# MT6816_Angle_Encoder.net
KiCad netlist of a schematic drawn in Altium Designer
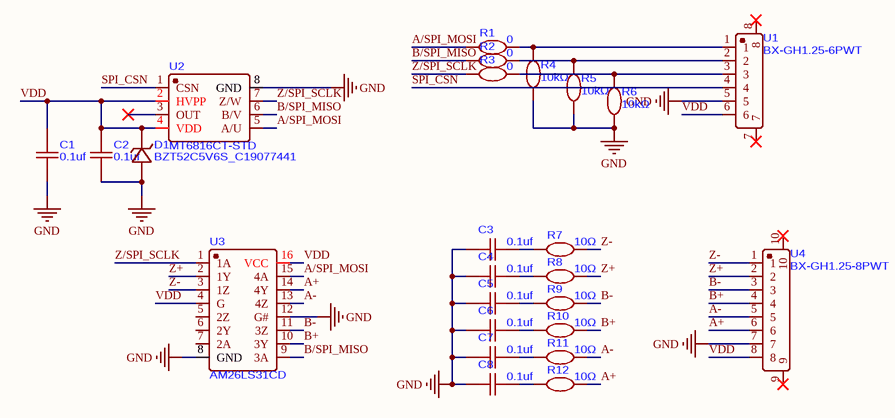
[diagram p0: MT6816_Angle_Encoder.SchDoc]

(export (version "E")
  (design (tool "Eeschema 10.0.6"))
  (components
    (comp (ref "C1")
      (value "0.1uf")
      (footprint "C0402")
      (libsource (lib "MT6816_Angle_Encoder") (part "CC0402KRX6S5BB225"))
    )
    (comp (ref "C2")
      (value "0.1uf")
      (footprint "C0402")
      (libsource (lib "MT6816_Angle_Encoder") (part "CC0402KRX6S5BB225"))
    )
    (comp (ref "C3")
      (value "0.1uf")
      (footprint "C0402")
      (libsource (lib "MT6816_Angle_Encoder") (part "CC0402KRX6S5BB225"))
    )
    (comp (ref "C4")
      (value "0.1uf")
      (footprint "C0402")
      (libsource (lib "MT6816_Angle_Encoder") (part "CC0402KRX6S5BB225"))
    )
    (comp (ref "C5")
      (value "0.1uf")
      (footprint "C0402")
      (libsource (lib "MT6816_Angle_Encoder") (part "CC0402KRX6S5BB225"))
    )
    (comp (ref "C6")
      (value "0.1uf")
      (footprint "C0402")
      (libsource (lib "MT6816_Angle_Encoder") (part "CC0402KRX6S5BB225"))
    )
    (comp (ref "C7")
      (value "0.1uf")
      (footprint "C0402")
      (libsource (lib "MT6816_Angle_Encoder") (part "CC0402KRX6S5BB225"))
    )
    (comp (ref "C8")
      (value "0.1uf")
      (footprint "C0402")
      (libsource (lib "MT6816_Angle_Encoder") (part "CC0402KRX6S5BB225"))
    )
    (comp (ref "D1")
      (value "BZT52C5V6S_C19077441")
      (footprint "SOD-323_L1.7-W1.3-LS2.6-RD")
      (libsource (lib "MT6816_Angle_Encoder") (part "BZT52C5V6S_C19077441"))
    )
    (comp (ref "R1")
      (value "0")
      (footprint "R0402")
      (libsource (lib "MT6816_Angle_Encoder") (part "PTFR0402B30K0P9"))
    )
    (comp (ref "R2")
      (value "0")
      (footprint "R0402")
      (libsource (lib "MT6816_Angle_Encoder") (part "PTFR0402B30K0P9"))
    )
    (comp (ref "R3")
      (value "0")
      (footprint "R0402")
      (libsource (lib "MT6816_Angle_Encoder") (part "PTFR0402B30K0P9"))
    )
    (comp (ref "R4")
      (value "10kΩ")
      (footprint "R0402")
      (libsource (lib "MT6816_Angle_Encoder") (part "PTFR0402B30K0P9"))
    )
    (comp (ref "R5")
      (value "10kΩ")
      (footprint "R0402")
      (libsource (lib "MT6816_Angle_Encoder") (part "PTFR0402B30K0P9"))
    )
    (comp (ref "R6")
      (value "10kΩ")
      (footprint "R0402")
      (libsource (lib "MT6816_Angle_Encoder") (part "PTFR0402B30K0P9"))
    )
    (comp (ref "R7")
      (value "10Ω")
      (footprint "R0402")
      (libsource (lib "MT6816_Angle_Encoder") (part "PTFR0402B30K0P9"))
    )
    (comp (ref "R8")
      (value "10Ω")
      (footprint "R0402")
      (libsource (lib "MT6816_Angle_Encoder") (part "PTFR0402B30K0P9"))
    )
    (comp (ref "R9")
      (value "10Ω")
      (footprint "R0402")
      (libsource (lib "MT6816_Angle_Encoder") (part "PTFR0402B30K0P9"))
    )
    (comp (ref "R10")
      (value "10Ω")
      (footprint "R0402")
      (libsource (lib "MT6816_Angle_Encoder") (part "PTFR0402B30K0P9"))
    )
    (comp (ref "R11")
      (value "10Ω")
      (footprint "R0402")
      (libsource (lib "MT6816_Angle_Encoder") (part "PTFR0402B30K0P9"))
    )
    (comp (ref "R12")
      (value "10Ω")
      (footprint "R0402")
      (libsource (lib "MT6816_Angle_Encoder") (part "PTFR0402B30K0P9"))
    )
    (comp (ref "U1")
      (value "BX-GH1.25-6PWT")
      (footprint "CONN-SMD_6P-P1.25_BX-GH1.25-6PWT")
      (libsource (lib "MT6816_Angle_Encoder") (part "BX-GH1.25-6PWT"))
    )
    (comp (ref "U2")
      (value "MT6816CT-STD")
      (footprint "SOP-8_L4.9-W3.9-P1.27-LS6.0-BL")
      (libsource (lib "MT6816_Angle_Encoder") (part "MT6816CT-STD"))
    )
    (comp (ref "U3")
      (value "AM26LS31CD")
      (footprint "SOIC-16_L9.9-W3.9-P1.27-LS6.0-BL")
      (libsource (lib "MT6816_Angle_Encoder") (part "AM26LS31CD"))
    )
    (comp (ref "U4")
      (value "BX-GH1.25-8PWT")
      (footprint "CONN-SMD_8P-P1.25_BX-GH1.25-8PWT")
      (libsource (lib "MT6816_Angle_Encoder") (part "BX-GH1.25-8PWT"))
    )
  )
  (nets
    (net (code "1") (name "/A+") (class "Default")
      (node (ref "R12") (pin "2") (pinfunction "2_2") (pintype "passive"))
      (node (ref "U3") (pin "14") (pinfunction "4Y_14") (pintype "passive"))
      (node (ref "U4") (pin "6") (pinfunction "6_6") (pintype "passive"))
    )
    (net (code "2") (name "/A-") (class "Default")
      (node (ref "R11") (pin "2") (pinfunction "2_2") (pintype "passive"))
      (node (ref "U3") (pin "13") (pinfunction "4Z_13") (pintype "passive"))
      (node (ref "U4") (pin "5") (pinfunction "5_5") (pintype "passive"))
    )
    (net (code "3") (name "/A{slash}SPI_MOSI") (class "Default")
      (node (ref "R1") (pin "2") (pinfunction "2_2") (pintype "passive"))
      (node (ref "U2") (pin "5") (pinfunction "A/U_5") (pintype "passive"))
      (node (ref "U3") (pin "15") (pinfunction "4A_15") (pintype "passive"))
    )
    (net (code "4") (name "/B+") (class "Default")
      (node (ref "R10") (pin "2") (pinfunction "2_2") (pintype "passive"))
      (node (ref "U3") (pin "10") (pinfunction "3Y_10") (pintype "passive"))
      (node (ref "U4") (pin "4") (pinfunction "4_4") (pintype "passive"))
    )
    (net (code "5") (name "/B-") (class "Default")
      (node (ref "R9") (pin "2") (pinfunction "2_2") (pintype "passive"))
      (node (ref "U3") (pin "11") (pinfunction "3Z_11") (pintype "passive"))
      (node (ref "U4") (pin "3") (pinfunction "3_3") (pintype "passive"))
    )
    (net (code "6") (name "/B{slash}SPI_MISO") (class "Default")
      (node (ref "R2") (pin "2") (pinfunction "2_2") (pintype "passive"))
      (node (ref "U2") (pin "6") (pinfunction "B/V_6") (pintype "passive"))
      (node (ref "U3") (pin "9") (pinfunction "3A_9") (pintype "passive"))
    )
    (net (code "7") (name "/SPI_CSN") (class "Default")
      (node (ref "U1") (pin "4") (pinfunction "4_4") (pintype "passive"))
      (node (ref "U2") (pin "1") (pinfunction "CSN_1") (pintype "passive"))
    )
    (net (code "8") (name "/VDD") (class "Default")
      (node (ref "C1") (pin "2") (pinfunction "2_2") (pintype "passive"))
      (node (ref "C2") (pin "2") (pinfunction "2_2") (pintype "passive"))
      (node (ref "D1") (pin "1") (pinfunction "K_1") (pintype "passive"))
      (node (ref "U1") (pin "6") (pinfunction "6_6") (pintype "passive"))
      (node (ref "U2") (pin "2") (pinfunction "HVPP_2") (pintype "passive"))
      (node (ref "U2") (pin "4") (pinfunction "VDD_4") (pintype "passive"))
      (node (ref "U3") (pin "16") (pinfunction "VCC_16") (pintype "passive"))
      (node (ref "U3") (pin "4") (pinfunction "G_4") (pintype "passive"))
      (node (ref "U4") (pin "8") (pinfunction "8_8") (pintype "passive"))
    )
    (net (code "9") (name "/Z+") (class "Default")
      (node (ref "R8") (pin "2") (pinfunction "2_2") (pintype "passive"))
      (node (ref "U3") (pin "2") (pinfunction "1Y_2") (pintype "passive"))
      (node (ref "U4") (pin "2") (pinfunction "2_2") (pintype "passive"))
    )
    (net (code "10") (name "/Z-") (class "Default")
      (node (ref "R7") (pin "2") (pinfunction "2_2") (pintype "passive"))
      (node (ref "U3") (pin "3") (pinfunction "1Z_3") (pintype "passive"))
      (node (ref "U4") (pin "1") (pinfunction "1_1") (pintype "passive"))
    )
    (net (code "11") (name "/Z{slash}SPI_SCLK") (class "Default")
      (node (ref "R3") (pin "2") (pinfunction "2_2") (pintype "passive"))
      (node (ref "U2") (pin "7") (pinfunction "Z/W_7") (pintype "passive"))
      (node (ref "U3") (pin "1") (pinfunction "1A_1") (pintype "passive"))
    )
    (net (code "12") (name "GND") (class "Default")
      (node (ref "C1") (pin "1") (pinfunction "1_1") (pintype "passive"))
      (node (ref "C2") (pin "1") (pinfunction "1_1") (pintype "passive"))
      (node (ref "C3") (pin "1") (pinfunction "1_1") (pintype "passive"))
      (node (ref "C4") (pin "1") (pinfunction "1_1") (pintype "passive"))
      (node (ref "C5") (pin "1") (pinfunction "1_1") (pintype "passive"))
      (node (ref "C6") (pin "1") (pinfunction "1_1") (pintype "passive"))
      (node (ref "C7") (pin "1") (pinfunction "1_1") (pintype "passive"))
      (node (ref "C8") (pin "1") (pinfunction "1_1") (pintype "passive"))
      (node (ref "D1") (pin "2") (pinfunction "A_2") (pintype "passive"))
      (node (ref "R4") (pin "1") (pinfunction "1_1") (pintype "passive"))
      (node (ref "R5") (pin "1") (pinfunction "1_1") (pintype "passive"))
      (node (ref "R6") (pin "1") (pinfunction "1_1") (pintype "passive"))
      (node (ref "U1") (pin "5") (pinfunction "5_5") (pintype "passive"))
      (node (ref "U2") (pin "8") (pinfunction "GND_8") (pintype "passive"))
      (node (ref "U3") (pin "12") (pinfunction "G#_12") (pintype "passive"))
      (node (ref "U3") (pin "8") (pinfunction "GND_8") (pintype "passive"))
      (node (ref "U4") (pin "7") (pinfunction "7_7") (pintype "passive"))
    )
    (net (code "13") (name "Net-(C3-Pad2)") (class "Default")
      (node (ref "C3") (pin "2") (pinfunction "2_2") (pintype "passive"))
      (node (ref "R7") (pin "1") (pinfunction "1_1") (pintype "passive"))
    )
    (net (code "14") (name "Net-(C4-Pad2)") (class "Default")
      (node (ref "C4") (pin "2") (pinfunction "2_2") (pintype "passive"))
      (node (ref "R8") (pin "1") (pinfunction "1_1") (pintype "passive"))
    )
    (net (code "15") (name "Net-(C5-Pad2)") (class "Default")
      (node (ref "C5") (pin "2") (pinfunction "2_2") (pintype "passive"))
      (node (ref "R9") (pin "1") (pinfunction "1_1") (pintype "passive"))
    )
    (net (code "16") (name "Net-(C6-Pad2)") (class "Default")
      (node (ref "C6") (pin "2") (pinfunction "2_2") (pintype "passive"))
      (node (ref "R10") (pin "1") (pinfunction "1_1") (pintype "passive"))
    )
    (net (code "17") (name "Net-(C7-Pad2)") (class "Default")
      (node (ref "C7") (pin "2") (pinfunction "2_2") (pintype "passive"))
      (node (ref "R11") (pin "1") (pinfunction "1_1") (pintype "passive"))
    )
    (net (code "18") (name "Net-(C8-Pad2)") (class "Default")
      (node (ref "C8") (pin "2") (pinfunction "2_2") (pintype "passive"))
      (node (ref "R12") (pin "1") (pinfunction "1_1") (pintype "passive"))
    )
    (net (code "19") (name "Net-(R1-Pad1)") (class "Default")
      (node (ref "R1") (pin "1") (pinfunction "1_1") (pintype "passive"))
      (node (ref "R4") (pin "2") (pinfunction "2_2") (pintype "passive"))
      (node (ref "U1") (pin "1") (pinfunction "1_1") (pintype "passive"))
    )
    (net (code "20") (name "Net-(R2-Pad1)") (class "Default")
      (node (ref "R2") (pin "1") (pinfunction "1_1") (pintype "passive"))
      (node (ref "R5") (pin "2") (pinfunction "2_2") (pintype "passive"))
      (node (ref "U1") (pin "2") (pinfunction "2_2") (pintype "passive"))
    )
    (net (code "21") (name "Net-(R3-Pad1)") (class "Default")
      (node (ref "R3") (pin "1") (pinfunction "1_1") (pintype "passive"))
      (node (ref "R6") (pin "2") (pinfunction "2_2") (pintype "passive"))
      (node (ref "U1") (pin "3") (pinfunction "3_3") (pintype "passive"))
    )
    (net (code "22") (name "unconnected-(U1-Pad7)") (class "Default")
      (node (ref "U1") (pin "7") (pinfunction "7_7") (pintype "passive+no_connect"))
    )
    (net (code "23") (name "unconnected-(U1-Pad8)") (class "Default")
      (node (ref "U1") (pin "8") (pinfunction "8_8") (pintype "passive+no_connect"))
    )
    (net (code "24") (name "unconnected-(U2-OUT-Pad3)") (class "Default")
      (node (ref "U2") (pin "3") (pinfunction "OUT_3") (pintype "passive+no_connect"))
    )
    (net (code "25") (name "unconnected-(U3-2A-Pad7)") (class "Default")
      (node (ref "U3") (pin "7") (pinfunction "2A_7") (pintype "passive"))
    )
    (net (code "26") (name "unconnected-(U3-2Y-Pad6)") (class "Default")
      (node (ref "U3") (pin "6") (pinfunction "2Y_6") (pintype "passive"))
    )
    (net (code "27") (name "unconnected-(U3-2Z-Pad5)") (class "Default")
      (node (ref "U3") (pin "5") (pinfunction "2Z_5") (pintype "passive"))
    )
    (net (code "28") (name "unconnected-(U4-Pad9)") (class "Default")
      (node (ref "U4") (pin "9") (pinfunction "9_9") (pintype "passive+no_connect"))
    )
    (net (code "29") (name "unconnected-(U4-Pad10)") (class "Default")
      (node (ref "U4") (pin "10") (pinfunction "10_10") (pintype "passive+no_connect"))
    )
  )
)
